# moire_v1_1.net
KiCad netlist of a schematic drawn in EAGLE
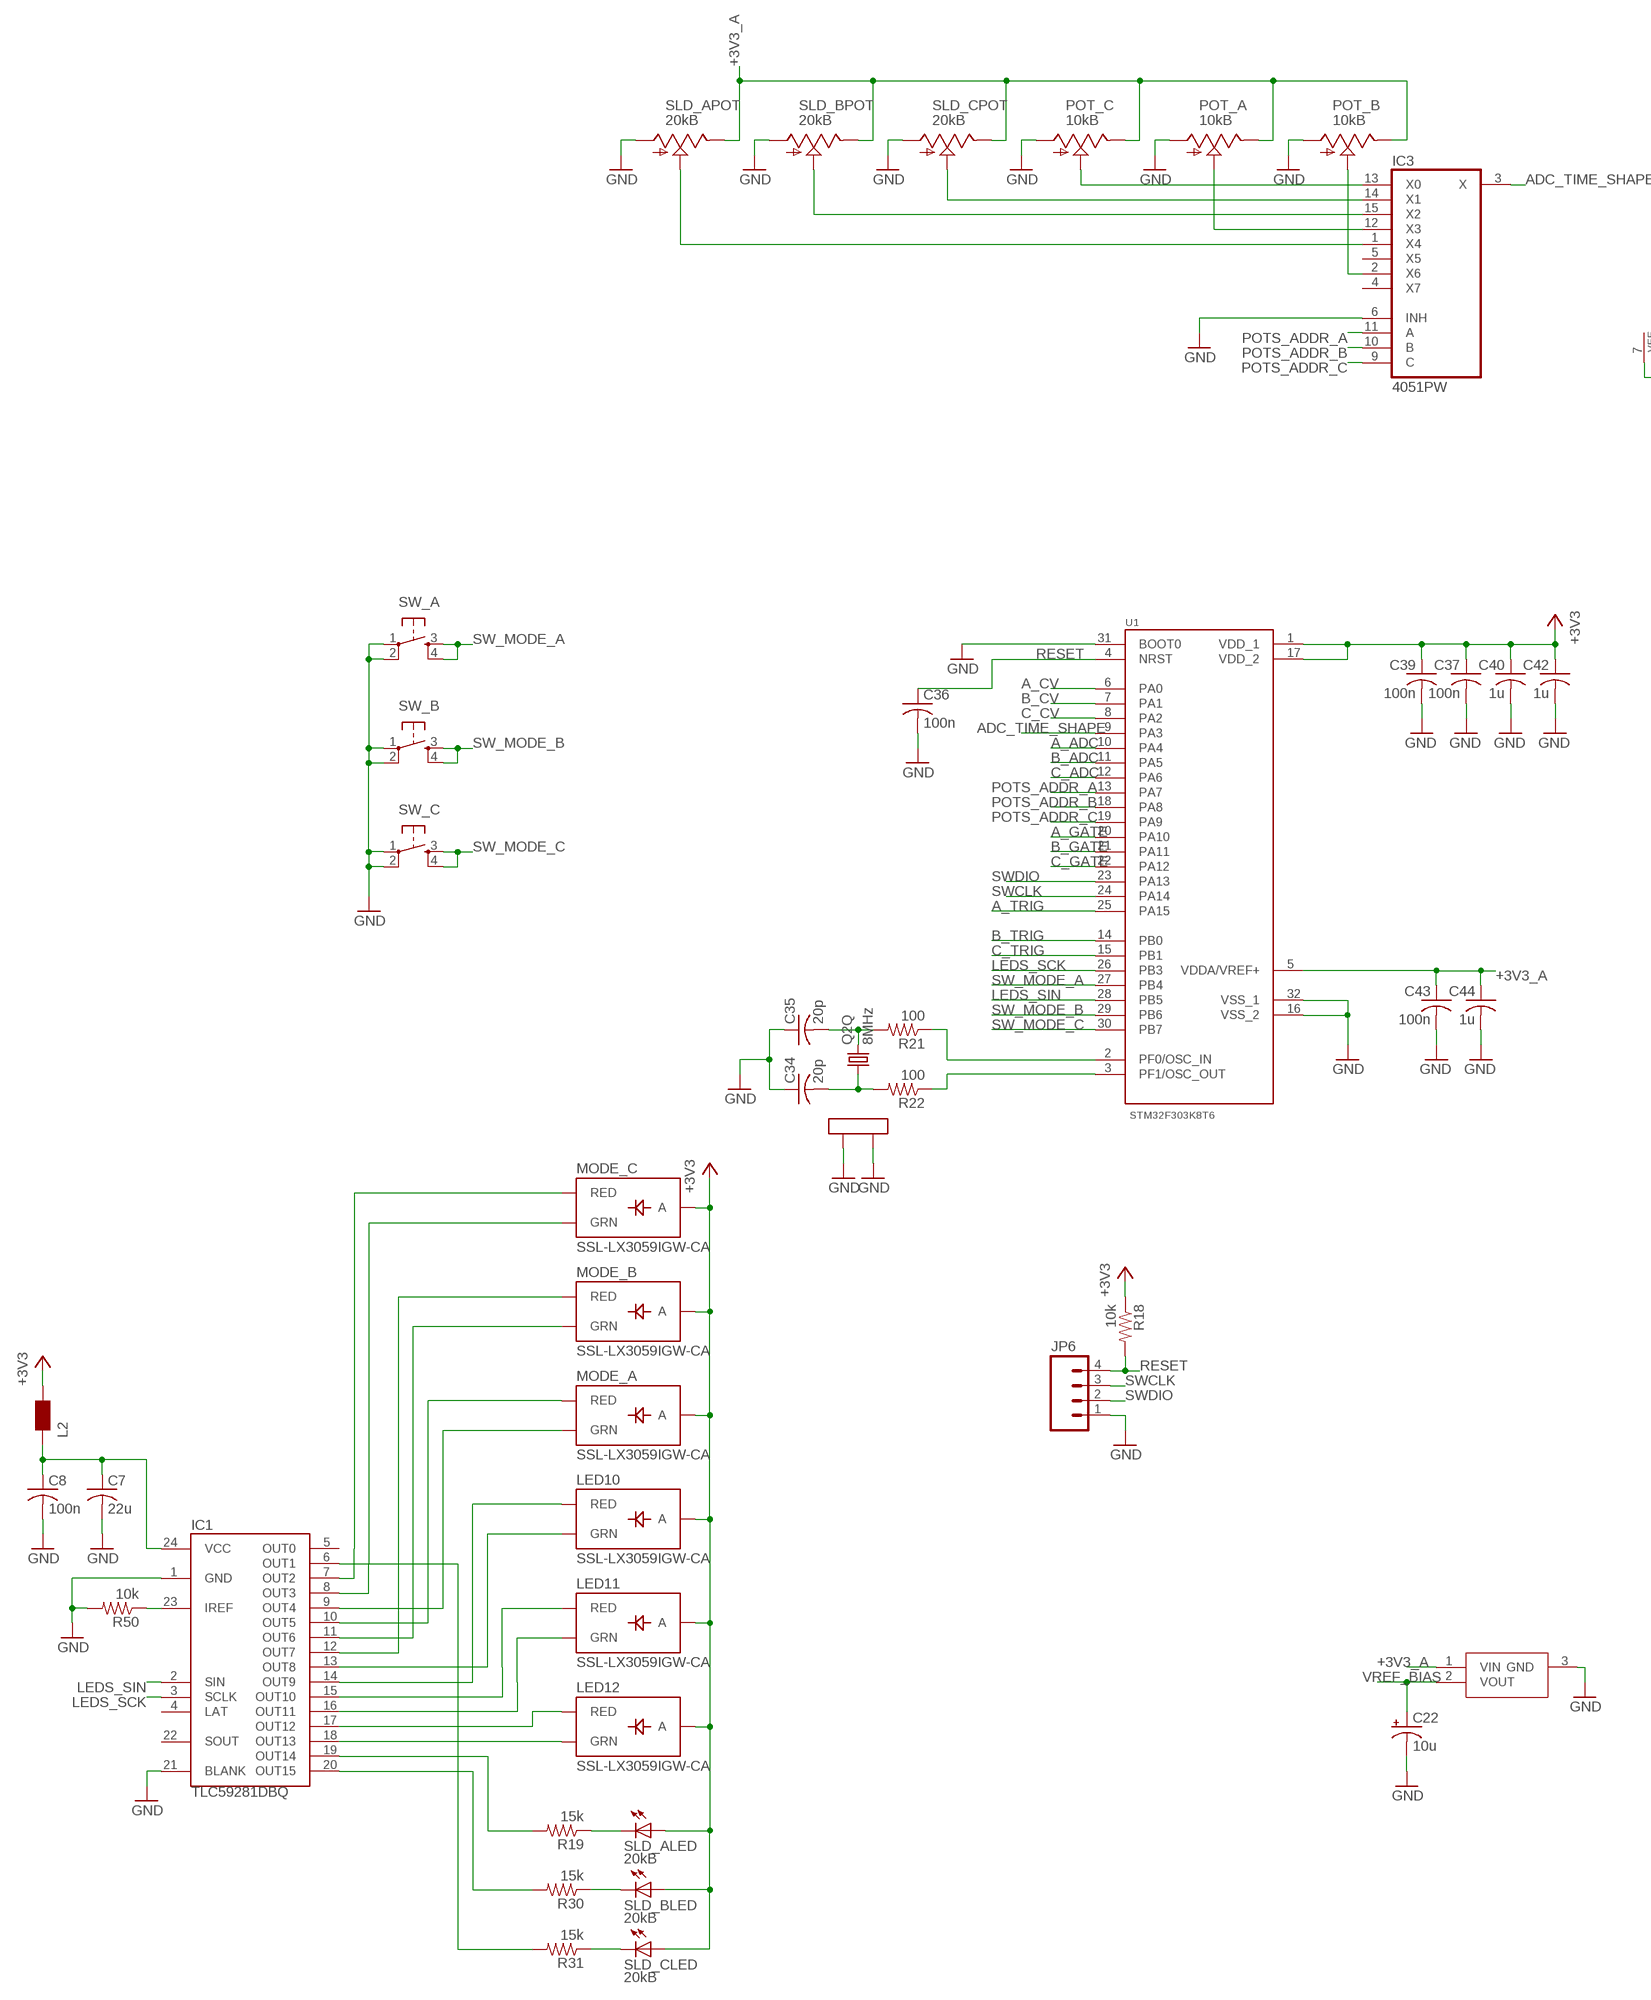
[diagram p0: schematic, sheet 1, part 1 of 2]
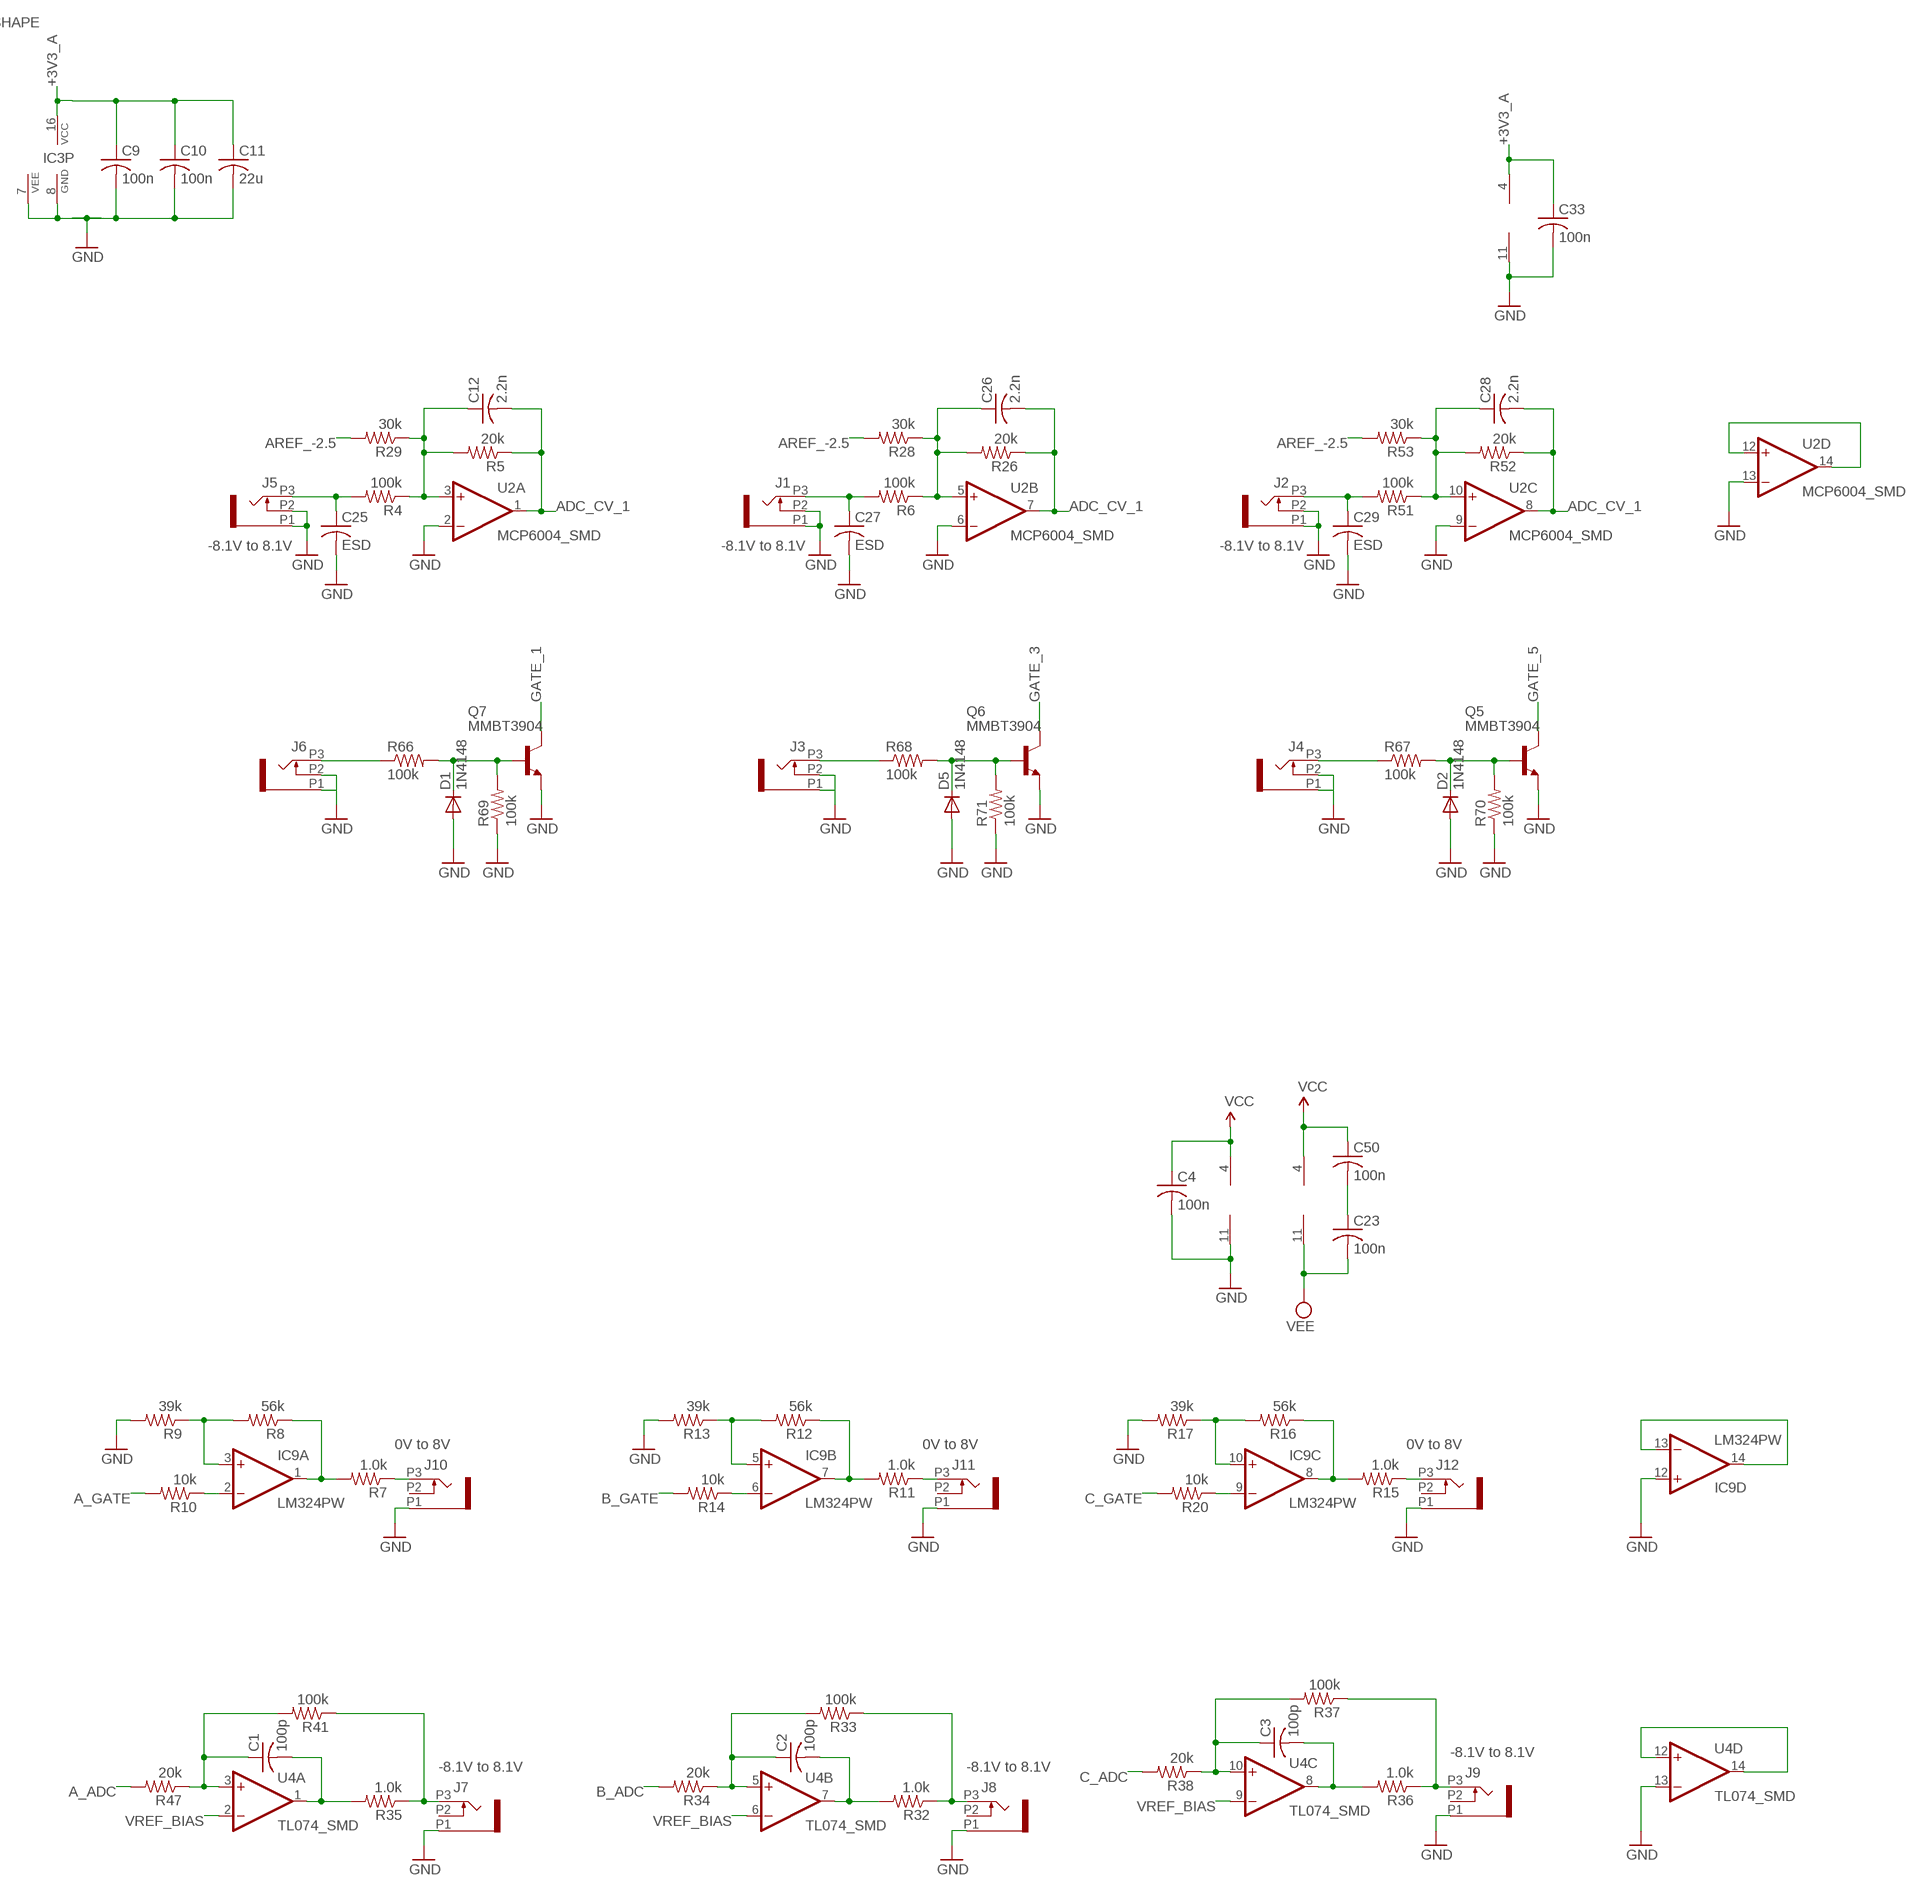
[diagram p1: schematic, sheet 1, part 2 of 2]
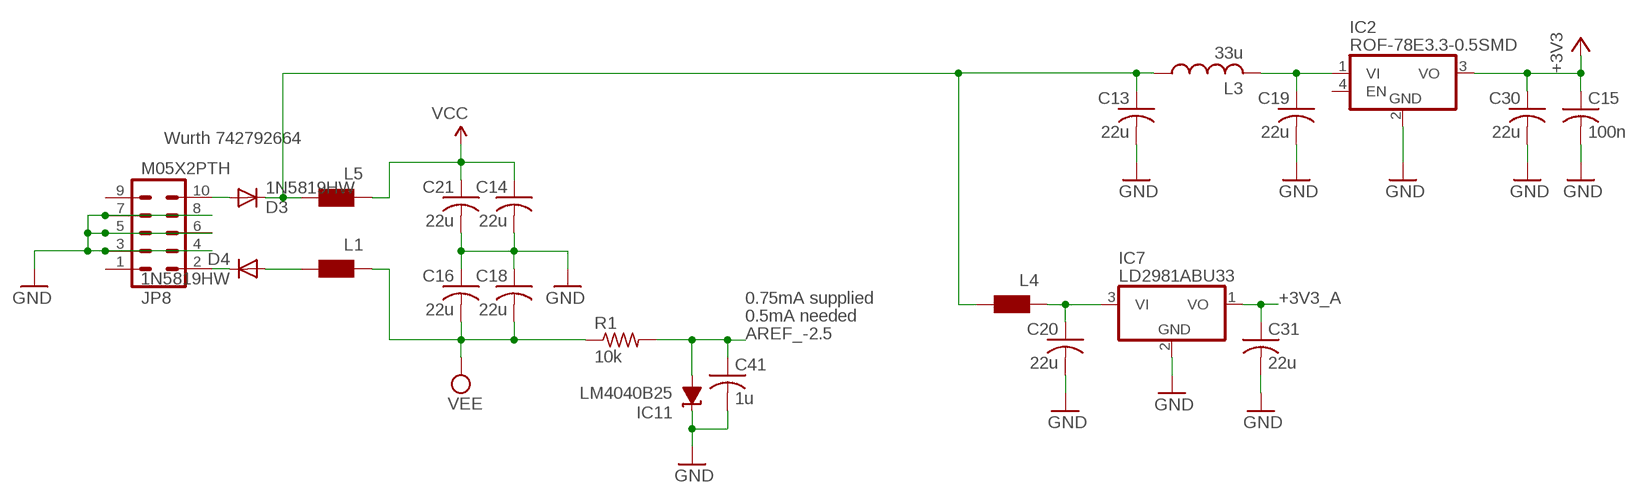
[diagram p2: schematic, sheet 2]

(export (version "E")
  (design (tool "Eeschema 10.0.6"))
  (components
    (comp (ref "C1")
      (value "100p")
      (footprint "eagle-import:C0603")
      (libsource (lib "eagle-import") (part "C-USC0603"))
    )
    (comp (ref "C2")
      (value "100p")
      (footprint "eagle-import:C0603")
      (libsource (lib "eagle-import") (part "C-USC0603"))
    )
    (comp (ref "C3")
      (value "100p")
      (footprint "eagle-import:C0603")
      (libsource (lib "eagle-import") (part "C-USC0603"))
    )
    (comp (ref "C4")
      (value "100n")
      (footprint "eagle-import:C0402")
      (libsource (lib "eagle-import") (part "C-USC0402"))
    )
    (comp (ref "C7")
      (value "22u")
      (footprint "eagle-import:C1206")
      (libsource (lib "eagle-import") (part "C-USC1206"))
    )
    (comp (ref "C8")
      (value "100n")
      (footprint "eagle-import:C0603")
      (libsource (lib "eagle-import") (part "C-USC0603"))
    )
    (comp (ref "C9")
      (value "100n")
      (footprint "eagle-import:C0603")
      (libsource (lib "eagle-import") (part "C-USC0603"))
    )
    (comp (ref "C10")
      (value "100n")
      (footprint "eagle-import:C0603")
      (libsource (lib "eagle-import") (part "C-USC0603"))
    )
    (comp (ref "C11")
      (value "22u")
      (footprint "eagle-import:C1206")
      (libsource (lib "eagle-import") (part "C-USC1206"))
    )
    (comp (ref "C12")
      (value "2.2n")
      (footprint "eagle-import:C0402")
      (libsource (lib "eagle-import") (part "C-USC0402"))
    )
    (comp (ref "C22")
      (value "10u")
      (footprint "eagle-import:PANASONIC_A")
      (libsource (lib "eagle-import") (part "CPOL-USA"))
    )
    (comp (ref "C23")
      (value "100n")
      (footprint "eagle-import:C0603")
      (libsource (lib "eagle-import") (part "C-USC0603"))
    )
    (comp (ref "C25")
      (value "ESD")
      (footprint "eagle-import:C0603")
      (libsource (lib "eagle-import") (part "C-USC0603"))
    )
    (comp (ref "C26")
      (value "2.2n")
      (footprint "eagle-import:C0402")
      (libsource (lib "eagle-import") (part "C-USC0402"))
    )
    (comp (ref "C27")
      (value "ESD")
      (footprint "eagle-import:C0603")
      (libsource (lib "eagle-import") (part "C-USC0603"))
    )
    (comp (ref "C28")
      (value "2.2n")
      (footprint "eagle-import:C0402")
      (libsource (lib "eagle-import") (part "C-USC0402"))
    )
    (comp (ref "C29")
      (value "ESD")
      (footprint "eagle-import:C0603")
      (libsource (lib "eagle-import") (part "C-USC0603"))
    )
    (comp (ref "C33")
      (value "100n")
      (footprint "eagle-import:C0603")
      (libsource (lib "eagle-import") (part "C-USC0603"))
    )
    (comp (ref "C34")
      (value "20p")
      (footprint "eagle-import:C0603")
      (libsource (lib "eagle-import") (part "C-USC0603"))
    )
    (comp (ref "C35")
      (value "20p")
      (footprint "eagle-import:C0603")
      (libsource (lib "eagle-import") (part "C-USC0603"))
    )
    (comp (ref "C36")
      (value "100n")
      (footprint "eagle-import:C0603")
      (libsource (lib "eagle-import") (part "C-USC0603"))
    )
    (comp (ref "C37")
      (value "100n")
      (footprint "eagle-import:C0603")
      (libsource (lib "eagle-import") (part "C-USC0603"))
    )
    (comp (ref "C39")
      (value "100n")
      (footprint "eagle-import:C0603")
      (libsource (lib "eagle-import") (part "C-USC0603"))
    )
    (comp (ref "C40")
      (value "1u")
      (footprint "eagle-import:C0603")
      (libsource (lib "eagle-import") (part "C-USC0603"))
    )
    (comp (ref "C42")
      (value "1u")
      (footprint "eagle-import:C0603")
      (libsource (lib "eagle-import") (part "C-USC0603"))
    )
    (comp (ref "C43")
      (value "100n")
      (footprint "eagle-import:C0603")
      (libsource (lib "eagle-import") (part "C-USC0603"))
    )
    (comp (ref "C44")
      (value "1u")
      (footprint "eagle-import:C0603")
      (libsource (lib "eagle-import") (part "C-USC0603"))
    )
    (comp (ref "C50")
      (value "100n")
      (footprint "eagle-import:C0603")
      (libsource (lib "eagle-import") (part "C-USC0603"))
    )
    (comp (ref "D1")
      (value "1N4148")
      (footprint "eagle-import:SOD523")
      (libsource (lib "eagle-import") (part "DIODE-SOD523"))
    )
    (comp (ref "D2")
      (value "1N4148")
      (footprint "eagle-import:SOD523")
      (libsource (lib "eagle-import") (part "DIODE-SOD523"))
    )
    (comp (ref "D5")
      (value "1N4148")
      (footprint "eagle-import:SOD523")
      (libsource (lib "eagle-import") (part "DIODE-SOD523"))
    )
    (comp (ref "IC1")
      (value "TLC59281DBQ")
      (footprint "eagle-import:TSSOP24_0635")
      (libsource (lib "eagle-import") (part "TLC59281DBQ"))
    )
    (comp (ref "IC3")
      (value "4051PW")
      (footprint "eagle-import:TSSOP16_065")
      (libsource (lib "eagle-import") (part "4051PW"))
    )
    (comp (ref "IC4")
      (value "LM324PW")
      (footprint "eagle-import:TSSOP14_065")
      (libsource (lib "eagle-import") (part "TL074PW"))
    )
    (comp (ref "IC9")
      (value "LM324PW")
      (footprint "eagle-import:TSSOP14_065")
      (libsource (lib "eagle-import") (part "TL074PW"))
    )
    (comp (ref "J1")
      (value "PJ301_THONKICONN6")
      (footprint "eagle-import:WQP_PJ_301M6")
      (libsource (lib "eagle-import") (part "PJ301_THONKICONN6"))
    )
    (comp (ref "J2")
      (value "PJ301_THONKICONN6")
      (footprint "eagle-import:WQP_PJ_301M6")
      (libsource (lib "eagle-import") (part "PJ301_THONKICONN6"))
    )
    (comp (ref "J3")
      (value "PJ301_THONKICONN6")
      (footprint "eagle-import:WQP_PJ_301M6")
      (libsource (lib "eagle-import") (part "PJ301_THONKICONN6"))
    )
    (comp (ref "J4")
      (value "PJ301_THONKICONN6")
      (footprint "eagle-import:WQP_PJ_301M6")
      (libsource (lib "eagle-import") (part "PJ301_THONKICONN6"))
    )
    (comp (ref "J5")
      (value "PJ301_THONKICONN6")
      (footprint "eagle-import:WQP_PJ_301M6")
      (libsource (lib "eagle-import") (part "PJ301_THONKICONN6"))
    )
    (comp (ref "J6")
      (value "PJ301_THONKICONN6")
      (footprint "eagle-import:WQP_PJ_301M6")
      (libsource (lib "eagle-import") (part "PJ301_THONKICONN6"))
    )
    (comp (ref "J7")
      (value "PJ301_THONKICONN6")
      (footprint "eagle-import:WQP_PJ_301M6")
      (libsource (lib "eagle-import") (part "PJ301_THONKICONN6"))
    )
    (comp (ref "J8")
      (value "PJ301_THONKICONN6")
      (footprint "eagle-import:WQP_PJ_301M6")
      (libsource (lib "eagle-import") (part "PJ301_THONKICONN6"))
    )
    (comp (ref "J9")
      (value "PJ301_THONKICONN6")
      (footprint "eagle-import:WQP_PJ_301M6")
      (libsource (lib "eagle-import") (part "PJ301_THONKICONN6"))
    )
    (comp (ref "J10")
      (value "PJ301_THONKICONN6")
      (footprint "eagle-import:WQP_PJ_301M6")
      (libsource (lib "eagle-import") (part "PJ301_THONKICONN6"))
    )
    (comp (ref "J11")
      (value "PJ301_THONKICONN6")
      (footprint "eagle-import:WQP_PJ_301M6")
      (libsource (lib "eagle-import") (part "PJ301_THONKICONN6"))
    )
    (comp (ref "J12")
      (value "PJ301_THONKICONN6")
      (footprint "eagle-import:WQP_PJ_301M6")
      (libsource (lib "eagle-import") (part "PJ301_THONKICONN6"))
    )
    (comp (ref "JP6")
      (value "M04PTH")
      (footprint "eagle-import:1X04")
      (libsource (lib "eagle-import") (part "M04PTH"))
    )
    (comp (ref "L2")
      (value "WE-CBF_0603")
      (footprint "eagle-import:0603")
      (libsource (lib "eagle-import") (part "WE-CBF_0603"))
    )
    (comp (ref "LED10")
      (value "SSL-LX3059IGW-CA")
      (footprint "eagle-import:LED-BICOLOR-THROUGHHOLE-LUMEX")
      (libsource (lib "eagle-import") (part "LED-BICOLOR-THROUGHHOLE-CA"))
    )
    (comp (ref "LED11")
      (value "SSL-LX3059IGW-CA")
      (footprint "eagle-import:LED-BICOLOR-THROUGHHOLE-LUMEX")
      (libsource (lib "eagle-import") (part "LED-BICOLOR-THROUGHHOLE-CA"))
    )
    (comp (ref "LED12")
      (value "SSL-LX3059IGW-CA")
      (footprint "eagle-import:LED-BICOLOR-THROUGHHOLE-LUMEX")
      (libsource (lib "eagle-import") (part "LED-BICOLOR-THROUGHHOLE-CA"))
    )
    (comp (ref "MODE_A")
      (value "SSL-LX3059IGW-CA")
      (footprint "eagle-import:LED-BICOLOR-THROUGHHOLE-LUMEX")
      (libsource (lib "eagle-import") (part "LED-BICOLOR-THROUGHHOLE-CA"))
    )
    (comp (ref "MODE_B")
      (value "SSL-LX3059IGW-CA")
      (footprint "eagle-import:LED-BICOLOR-THROUGHHOLE-LUMEX")
      (libsource (lib "eagle-import") (part "LED-BICOLOR-THROUGHHOLE-CA"))
    )
    (comp (ref "MODE_C")
      (value "SSL-LX3059IGW-CA")
      (footprint "eagle-import:LED-BICOLOR-THROUGHHOLE-LUMEX")
      (libsource (lib "eagle-import") (part "LED-BICOLOR-THROUGHHOLE-CA"))
    )
    (comp (ref "POT_A")
      (value "10kB")
      (footprint "eagle-import:ALPS_POT_VERTICAL_PS")
      (libsource (lib "eagle-import") (part "POT_USVERTICAL_PS"))
    )
    (comp (ref "POT_B")
      (value "10kB")
      (footprint "eagle-import:ALPS_POT_VERTICAL_PS")
      (libsource (lib "eagle-import") (part "POT_USVERTICAL_PS"))
    )
    (comp (ref "POT_C")
      (value "10kB")
      (footprint "eagle-import:ALPS_POT_VERTICAL_PS")
      (libsource (lib "eagle-import") (part "POT_USVERTICAL_PS"))
    )
    (comp (ref "Q2")
      (value "8MHz")
      (footprint "eagle-import:CTS406")
      (libsource (lib "eagle-import") (part "CRYSTAL"))
    )
    (comp (ref "Q5")
      (value "MMBT3904")
      (footprint "eagle-import:SOT23-BEC")
      (libsource (lib "eagle-import") (part "-NPN-SOT23-BECMMBT3904LT1"))
    )
    (comp (ref "Q6")
      (value "MMBT3904")
      (footprint "eagle-import:SOT23-BEC")
      (libsource (lib "eagle-import") (part "-NPN-SOT23-BECMMBT3904LT1"))
    )
    (comp (ref "Q7")
      (value "MMBT3904")
      (footprint "eagle-import:SOT23-BEC")
      (libsource (lib "eagle-import") (part "-NPN-SOT23-BECMMBT3904LT1"))
    )
    (comp (ref "R4")
      (value "100k")
      (footprint "eagle-import:R0402")
      (libsource (lib "eagle-import") (part "R-US_R0402"))
    )
    (comp (ref "R5")
      (value "20k")
      (footprint "eagle-import:R0402")
      (libsource (lib "eagle-import") (part "R-US_R0402"))
    )
    (comp (ref "R6")
      (value "100k")
      (footprint "eagle-import:R0402")
      (libsource (lib "eagle-import") (part "R-US_R0402"))
    )
    (comp (ref "R7")
      (value "1.0k")
      (footprint "eagle-import:R0603")
      (libsource (lib "eagle-import") (part "R-US_R0603"))
    )
    (comp (ref "R8")
      (value "56k")
      (footprint "eagle-import:R0402")
      (libsource (lib "eagle-import") (part "R-US_R0402"))
    )
    (comp (ref "R9")
      (value "39k")
      (footprint "eagle-import:R0402")
      (libsource (lib "eagle-import") (part "R-US_R0402"))
    )
    (comp (ref "R10")
      (value "10k")
      (footprint "eagle-import:R0402")
      (libsource (lib "eagle-import") (part "R-US_R0402"))
    )
    (comp (ref "R11")
      (value "1.0k")
      (footprint "eagle-import:R0603")
      (libsource (lib "eagle-import") (part "R-US_R0603"))
    )
    (comp (ref "R12")
      (value "56k")
      (footprint "eagle-import:R0402")
      (libsource (lib "eagle-import") (part "R-US_R0402"))
    )
    (comp (ref "R13")
      (value "39k")
      (footprint "eagle-import:R0402")
      (libsource (lib "eagle-import") (part "R-US_R0402"))
    )
    (comp (ref "R14")
      (value "10k")
      (footprint "eagle-import:R0402")
      (libsource (lib "eagle-import") (part "R-US_R0402"))
    )
    (comp (ref "R15")
      (value "1.0k")
      (footprint "eagle-import:R0603")
      (libsource (lib "eagle-import") (part "R-US_R0603"))
    )
    (comp (ref "R16")
      (value "56k")
      (footprint "eagle-import:R0402")
      (libsource (lib "eagle-import") (part "R-US_R0402"))
    )
    (comp (ref "R17")
      (value "39k")
      (footprint "eagle-import:R0402")
      (libsource (lib "eagle-import") (part "R-US_R0402"))
    )
    (comp (ref "R18")
      (value "10k")
      (footprint "eagle-import:R0603")
      (libsource (lib "eagle-import") (part "R-US_R0603"))
    )
    (comp (ref "R19")
      (value "15k")
      (footprint "eagle-import:R0603")
      (libsource (lib "eagle-import") (part "R-US_R0603"))
    )
    (comp (ref "R20")
      (value "10k")
      (footprint "eagle-import:R0402")
      (libsource (lib "eagle-import") (part "R-US_R0402"))
    )
    (comp (ref "R21")
      (value "100")
      (footprint "eagle-import:R0603")
      (libsource (lib "eagle-import") (part "R-US_R0603"))
    )
    (comp (ref "R22")
      (value "100")
      (footprint "eagle-import:R0603")
      (libsource (lib "eagle-import") (part "R-US_R0603"))
    )
    (comp (ref "R26")
      (value "20k")
      (footprint "eagle-import:R0402")
      (libsource (lib "eagle-import") (part "R-US_R0402"))
    )
    (comp (ref "R28")
      (value "30k")
      (footprint "eagle-import:R0402")
      (libsource (lib "eagle-import") (part "R-US_R0402"))
    )
    (comp (ref "R29")
      (value "30k")
      (footprint "eagle-import:R0402")
      (libsource (lib "eagle-import") (part "R-US_R0402"))
    )
    (comp (ref "R30")
      (value "15k")
      (footprint "eagle-import:R0603")
      (libsource (lib "eagle-import") (part "R-US_R0603"))
    )
    (comp (ref "R31")
      (value "15k")
      (footprint "eagle-import:R0603")
      (libsource (lib "eagle-import") (part "R-US_R0603"))
    )
    (comp (ref "R32")
      (value "1.0k")
      (footprint "eagle-import:R0603")
      (libsource (lib "eagle-import") (part "R-US_R0603"))
    )
    (comp (ref "R33")
      (value "100k")
      (footprint "eagle-import:R0603")
      (libsource (lib "eagle-import") (part "R-US_R0603"))
    )
    (comp (ref "R34")
      (value "20k")
      (footprint "eagle-import:R0603")
      (libsource (lib "eagle-import") (part "R-US_R0603"))
    )
    (comp (ref "R35")
      (value "1.0k")
      (footprint "eagle-import:R0603")
      (libsource (lib "eagle-import") (part "R-US_R0603"))
    )
    (comp (ref "R36")
      (value "1.0k")
      (footprint "eagle-import:R0603")
      (libsource (lib "eagle-import") (part "R-US_R0603"))
    )
    (comp (ref "R37")
      (value "100k")
      (footprint "eagle-import:R0603")
      (libsource (lib "eagle-import") (part "R-US_R0603"))
    )
    (comp (ref "R38")
      (value "20k")
      (footprint "eagle-import:R0603")
      (libsource (lib "eagle-import") (part "R-US_R0603"))
    )
    (comp (ref "R41")
      (value "100k")
      (footprint "eagle-import:R0603")
      (libsource (lib "eagle-import") (part "R-US_R0603"))
    )
    (comp (ref "R47")
      (value "20k")
      (footprint "eagle-import:R0603")
      (libsource (lib "eagle-import") (part "R-US_R0603"))
    )
    (comp (ref "R50")
      (value "10k")
      (footprint "eagle-import:R0603")
      (libsource (lib "eagle-import") (part "R-US_R0603"))
    )
    (comp (ref "R51")
      (value "100k")
      (footprint "eagle-import:R0402")
      (libsource (lib "eagle-import") (part "R-US_R0402"))
    )
    (comp (ref "R52")
      (value "20k")
      (footprint "eagle-import:R0402")
      (libsource (lib "eagle-import") (part "R-US_R0402"))
    )
    (comp (ref "R53")
      (value "30k")
      (footprint "eagle-import:R0402")
      (libsource (lib "eagle-import") (part "R-US_R0402"))
    )
    (comp (ref "R66")
      (value "100k")
      (footprint "eagle-import:R0402")
      (libsource (lib "eagle-import") (part "R-US_R0402"))
    )
    (comp (ref "R67")
      (value "100k")
      (footprint "eagle-import:R0402")
      (libsource (lib "eagle-import") (part "R-US_R0402"))
    )
    (comp (ref "R68")
      (value "100k")
      (footprint "eagle-import:R0402")
      (libsource (lib "eagle-import") (part "R-US_R0402"))
    )
    (comp (ref "R69")
      (value "100k")
      (footprint "eagle-import:R0402")
      (libsource (lib "eagle-import") (part "R-US_R0402"))
    )
    (comp (ref "R70")
      (value "100k")
      (footprint "eagle-import:R0402")
      (libsource (lib "eagle-import") (part "R-US_R0402"))
    )
    (comp (ref "R71")
      (value "100k")
      (footprint "eagle-import:R0402")
      (libsource (lib "eagle-import") (part "R-US_R0402"))
    )
    (comp (ref "SLD_A")
      (value "20kB")
      (footprint "eagle-import:BOURNS_SLIDER")
      (libsource (lib "eagle-import") (part "BOURNS_SLIDER"))
    )
    (comp (ref "SLD_B")
      (value "20kB")
      (footprint "eagle-import:BOURNS_SLIDER")
      (libsource (lib "eagle-import") (part "BOURNS_SLIDER"))
    )
    (comp (ref "SLD_C")
      (value "20kB")
      (footprint "eagle-import:BOURNS_SLIDER")
      (libsource (lib "eagle-import") (part "BOURNS_SLIDER"))
    )
    (comp (ref "SW_A")
      (value "TAC_SWITCHPTH")
      (footprint "eagle-import:TACTILE-PTH")
      (libsource (lib "eagle-import") (part "TAC_SWITCHPTH"))
    )
    (comp (ref "SW_B")
      (value "TAC_SWITCHPTH")
      (footprint "eagle-import:TACTILE-PTH")
      (libsource (lib "eagle-import") (part "TAC_SWITCHPTH"))
    )
    (comp (ref "SW_C")
      (value "TAC_SWITCHPTH")
      (footprint "eagle-import:TACTILE-PTH")
      (libsource (lib "eagle-import") (part "TAC_SWITCHPTH"))
    )
    (comp (ref "U$1")
      (value "ISL21010")
      (footprint "eagle-import:SOT-23-3")
      (libsource (lib "eagle-import") (part "ISL21010"))
    )
    (comp (ref "U1")
      (value "STM32F303K8T6")
      (footprint "eagle-import:QFP80P900X900X160-32N")
      (fields (field (name "MF") "STMicroelectronics"))
      (libsource (lib "eagle-import") (part "STM32F303K8T6"))
    )
    (comp (ref "U2")
      (value "MCP6004_SMD")
      (footprint "eagle-import:SO14")
      (libsource (lib "eagle-import") (part "MCP6004_SMD"))
    )
    (comp (ref "U4")
      (value "TL074_SMD")
      (footprint "eagle-import:SO14")
      (libsource (lib "eagle-import") (part "TL074_SMD"))
    )
    (comp (ref "C13")
      (value "22u")
      (footprint "eagle-import:C1206")
      (libsource (lib "eagle-import") (part "C-USC1206"))
    )
    (comp (ref "C14")
      (value "22u")
      (footprint "eagle-import:C1206")
      (libsource (lib "eagle-import") (part "C-USC1206"))
    )
    (comp (ref "C15")
      (value "100n")
      (footprint "eagle-import:C0402")
      (libsource (lib "eagle-import") (part "C-USC0402"))
    )
    (comp (ref "C16")
      (value "22u")
      (footprint "eagle-import:C1206")
      (libsource (lib "eagle-import") (part "C-USC1206"))
    )
    (comp (ref "C18")
      (value "22u")
      (footprint "eagle-import:C1206")
      (libsource (lib "eagle-import") (part "C-USC1206"))
    )
    (comp (ref "C19")
      (value "22u")
      (footprint "eagle-import:C1206")
      (libsource (lib "eagle-import") (part "C-USC1206"))
    )
    (comp (ref "C20")
      (value "22u")
      (footprint "eagle-import:C1206")
      (libsource (lib "eagle-import") (part "C-USC1206"))
    )
    (comp (ref "C21")
      (value "22u")
      (footprint "eagle-import:C1206")
      (libsource (lib "eagle-import") (part "C-USC1206"))
    )
    (comp (ref "C30")
      (value "22u")
      (footprint "eagle-import:C1206")
      (libsource (lib "eagle-import") (part "C-USC1206"))
    )
    (comp (ref "C31")
      (value "22u")
      (footprint "eagle-import:C1206")
      (libsource (lib "eagle-import") (part "C-USC1206"))
    )
    (comp (ref "C41")
      (value "1u")
      (footprint "eagle-import:C0402")
      (libsource (lib "eagle-import") (part "C-USC0402"))
    )
    (comp (ref "D3")
      (value "1N5819HW")
      (footprint "eagle-import:SOD123")
      (libsource (lib "eagle-import") (part "DIODE-SOD123"))
    )
    (comp (ref "D4")
      (value "1N5819HW")
      (footprint "eagle-import:SOD123")
      (libsource (lib "eagle-import") (part "DIODE-SOD123"))
    )
    (comp (ref "IC2")
      (value "ROF-78E3.3-0.5SMD")
      (footprint "eagle-import:ROF78EXX-0.5SMD")
      (libsource (lib "eagle-import") (part "ROF-78EXX-0.55SMD"))
    )
    (comp (ref "IC7")
      (value "LD2981ABU33")
      (footprint "eagle-import:SOT89")
      (libsource (lib "eagle-import") (part "LD2981ABU"))
    )
    (comp (ref "IC11")
      (value "LM4040B25")
      (footprint "eagle-import:DBZ_R-PDSO-G3")
      (libsource (lib "eagle-import") (part "LM4041DBZB12"))
    )
    (comp (ref "JP8")
      (value "M05X2PTH")
      (footprint "eagle-import:2X5-PTH")
      (libsource (lib "eagle-import") (part "M05X2PTH"))
    )
    (comp (ref "L1")
      (value "WE-CBF_0603")
      (footprint "eagle-import:0603")
      (libsource (lib "eagle-import") (part "WE-CBF_0603"))
    )
    (comp (ref "L3")
      (value "33u")
      (footprint "eagle-import:L2012C")
      (libsource (lib "eagle-import") (part "L-USL2012C"))
    )
    (comp (ref "L4")
      (value "WE-CBF_0603")
      (footprint "eagle-import:0603")
      (libsource (lib "eagle-import") (part "WE-CBF_0603"))
    )
    (comp (ref "L5")
      (value "WE-CBF_0603")
      (footprint "eagle-import:0603")
      (libsource (lib "eagle-import") (part "WE-CBF_0603"))
    )
    (comp (ref "R1")
      (value "10k")
      (footprint "eagle-import:R0402")
      (libsource (lib "eagle-import") (part "R-US_R0402"))
    )
  )
  (nets
    (net (code "1") (name "+3V3") (class "Default")
      (node (ref "C15") (pin "1") (pinfunction "1_1") (pintype "passive"))
      (node (ref "C30") (pin "1") (pinfunction "1_1") (pintype "passive"))
      (node (ref "C37") (pin "1") (pinfunction "1_1") (pintype "passive"))
      (node (ref "C39") (pin "1") (pinfunction "1_1") (pintype "passive"))
      (node (ref "C40") (pin "1") (pinfunction "1_1") (pintype "passive"))
      (node (ref "C42") (pin "1") (pinfunction "1_1") (pintype "passive"))
      (node (ref "IC2") (pin "3") (pinfunction "VO_3") (pintype "passive"))
      (node (ref "L2") (pin "2") (pinfunction "2_2") (pintype "passive"))
      (node (ref "LED10") (pin "A") (pinfunction "A_A") (pintype "bidirectional"))
      (node (ref "LED11") (pin "A") (pinfunction "A_A") (pintype "bidirectional"))
      (node (ref "LED12") (pin "A") (pinfunction "A_A") (pintype "bidirectional"))
      (node (ref "MODE_A") (pin "A") (pinfunction "A_A") (pintype "bidirectional"))
      (node (ref "MODE_B") (pin "A") (pinfunction "A_A") (pintype "bidirectional"))
      (node (ref "MODE_C") (pin "A") (pinfunction "A_A") (pintype "bidirectional"))
      (node (ref "R18") (pin "1") (pinfunction "1_1") (pintype "passive"))
      (node (ref "SLD_A") (pin "B") (pinfunction "A_B") (pintype "passive"))
      (node (ref "SLD_B") (pin "B") (pinfunction "A_B") (pintype "passive"))
      (node (ref "SLD_C") (pin "B") (pinfunction "A_B") (pintype "passive"))
      (node (ref "U1") (pin "1") (pinfunction "VDD_1_1") (pintype "power_in"))
      (node (ref "U1") (pin "17") (pinfunction "VDD_2_17") (pintype "power_in"))
    )
    (net (code "2") (name "+3V3_A") (class "Default")
      (node (ref "C10") (pin "1") (pinfunction "1_1") (pintype "passive"))
      (node (ref "C11") (pin "1") (pinfunction "1_1") (pintype "passive"))
      (node (ref "C31") (pin "1") (pinfunction "1_1") (pintype "passive"))
      (node (ref "C33") (pin "1") (pinfunction "1_1") (pintype "passive"))
      (node (ref "C43") (pin "1") (pinfunction "1_1") (pintype "passive"))
      (node (ref "C44") (pin "1") (pinfunction "1_1") (pintype "passive"))
      (node (ref "C9") (pin "1") (pinfunction "1_1") (pintype "passive"))
      (node (ref "IC3") (pin "16") (pinfunction "VCC_16") (pintype "power_in"))
      (node (ref "IC7") (pin "1") (pinfunction "VO_1") (pintype "passive"))
      (node (ref "POT_A") (pin "P$1") (pinfunction "E_P$1") (pintype "passive"))
      (node (ref "POT_B") (pin "P$1") (pinfunction "E_P$1") (pintype "passive"))
      (node (ref "POT_C") (pin "P$1") (pinfunction "E_P$1") (pintype "passive"))
      (node (ref "SLD_A") (pin "3") (pinfunction "E_3") (pintype "passive"))
      (node (ref "SLD_B") (pin "3") (pinfunction "E_3") (pintype "passive"))
      (node (ref "SLD_C") (pin "3") (pinfunction "E_3") (pintype "passive"))
      (node (ref "U$1") (pin "1") (pinfunction "VIN_1") (pintype "input"))
      (node (ref "U1") (pin "5") (pinfunction "VDDA/VREF+_5") (pintype "power_in"))
      (node (ref "U2") (pin "4") (pinfunction "V+_4") (pintype "power_in"))
    )
    (net (code "3") (name "ADC_CV_1") (class "Default")
      (node (ref "C12") (pin "2") (pinfunction "2_2") (pintype "passive"))
      (node (ref "C26") (pin "2") (pinfunction "2_2") (pintype "passive"))
      (node (ref "C28") (pin "2") (pinfunction "2_2") (pintype "passive"))
      (node (ref "R26") (pin "1") (pinfunction "1_1") (pintype "passive"))
      (node (ref "R5") (pin "1") (pinfunction "1_1") (pintype "passive"))
      (node (ref "R52") (pin "1") (pinfunction "1_1") (pintype "passive"))
      (node (ref "U2") (pin "1") (pinfunction "OUT_1") (pintype "output"))
      (node (ref "U2") (pin "7") (pinfunction "OUT_7") (pintype "output"))
      (node (ref "U2") (pin "8") (pinfunction "OUT_8") (pintype "output"))
    )
    (net (code "4") (name "ADC_TIME_SHAPE") (class "Default")
      (node (ref "IC3") (pin "3") (pinfunction "X_3") (pintype "bidirectional"))
      (node (ref "U1") (pin "9") (pinfunction "PA3_9") (pintype "bidirectional"))
    )
    (net (code "5") (name "AREF_-2.5") (class "Default")
      (node (ref "C41") (pin "1") (pinfunction "1_1") (pintype "passive"))
      (node (ref "IC11") (pin "2") (pinfunction "A_2") (pintype "passive"))
      (node (ref "R1") (pin "2") (pinfunction "2_2") (pintype "passive"))
      (node (ref "R28") (pin "2") (pinfunction "2_2") (pintype "passive"))
      (node (ref "R29") (pin "2") (pinfunction "2_2") (pintype "passive"))
      (node (ref "R53") (pin "2") (pinfunction "2_2") (pintype "passive"))
    )
    (net (code "6") (name "A_ADC") (class "Default")
      (node (ref "R47") (pin "2") (pinfunction "2_2") (pintype "passive"))
      (node (ref "U1") (pin "10") (pinfunction "PA4_10") (pintype "bidirectional"))
    )
    (net (code "7") (name "A_CV") (class "Default")
      (node (ref "U1") (pin "6") (pinfunction "PA0_6") (pintype "bidirectional"))
    )
    (net (code "8") (name "A_GATE") (class "Default")
      (node (ref "R10") (pin "2") (pinfunction "2_2") (pintype "passive"))
      (node (ref "U1") (pin "20") (pinfunction "PA10_20") (pintype "bidirectional"))
    )
    (net (code "9") (name "A_TRIG") (class "Default")
      (node (ref "U1") (pin "25") (pinfunction "PA15_25") (pintype "bidirectional"))
    )
    (net (code "10") (name "B_ADC") (class "Default")
      (node (ref "R34") (pin "2") (pinfunction "2_2") (pintype "passive"))
      (node (ref "U1") (pin "11") (pinfunction "PA5_11") (pintype "bidirectional"))
    )
    (net (code "11") (name "B_CV") (class "Default")
      (node (ref "U1") (pin "7") (pinfunction "PA1_7") (pintype "bidirectional"))
    )
    (net (code "12") (name "B_GATE") (class "Default")
      (node (ref "R14") (pin "2") (pinfunction "2_2") (pintype "passive"))
      (node (ref "U1") (pin "21") (pinfunction "PA11_21") (pintype "bidirectional"))
    )
    (net (code "13") (name "B_TRIG") (class "Default")
      (node (ref "U1") (pin "14") (pinfunction "PB0_14") (pintype "bidirectional"))
    )
    (net (code "14") (name "C_ADC") (class "Default")
      (node (ref "R38") (pin "2") (pinfunction "2_2") (pintype "passive"))
      (node (ref "U1") (pin "12") (pinfunction "PA6_12") (pintype "bidirectional"))
    )
    (net (code "15") (name "C_CV") (class "Default")
      (node (ref "U1") (pin "8") (pinfunction "PA2_8") (pintype "bidirectional"))
    )
    (net (code "16") (name "C_GATE") (class "Default")
      (node (ref "R20") (pin "2") (pinfunction "2_2") (pintype "passive"))
      (node (ref "U1") (pin "22") (pinfunction "PA12_22") (pintype "bidirectional"))
    )
    (net (code "17") (name "C_TRIG") (class "Default")
      (node (ref "U1") (pin "15") (pinfunction "PB1_15") (pintype "bidirectional"))
    )
    (net (code "18") (name "GATE_1") (class "Default")
      (node (ref "Q7") (pin "C") (pinfunction "C_C") (pintype "passive"))
    )
    (net (code "19") (name "GATE_3") (class "Default")
      (node (ref "Q6") (pin "C") (pinfunction "C_C") (pintype "passive"))
    )
    (net (code "20") (name "GATE_5") (class "Default")
      (node (ref "Q5") (pin "C") (pinfunction "C_C") (pintype "passive"))
    )
    (net (code "21") (name "GND") (class "Default")
      (node (ref "C10") (pin "2") (pinfunction "2_2") (pintype "passive"))
      (node (ref "C11") (pin "2") (pinfunction "2_2") (pintype "passive"))
      (node (ref "C13") (pin "2") (pinfunction "2_2") (pintype "passive"))
      (node (ref "C14") (pin "2") (pinfunction "2_2") (pintype "passive"))
      (node (ref "C15") (pin "2") (pinfunction "2_2") (pintype "passive"))
      (node (ref "C16") (pin "1") (pinfunction "1_1") (pintype "passive"))
      (node (ref "C18") (pin "1") (pinfunction "1_1") (pintype "passive"))
      (node (ref "C19") (pin "2") (pinfunction "2_2") (pintype "passive"))
      (node (ref "C20") (pin "2") (pinfunction "2_2") (pintype "passive"))
      (node (ref "C21") (pin "2") (pinfunction "2_2") (pintype "passive"))
      (node (ref "C22") (pin "-") (pinfunction "-_-") (pintype "passive"))
      (node (ref "C25") (pin "2") (pinfunction "2_2") (pintype "passive"))
      (node (ref "C27") (pin "2") (pinfunction "2_2") (pintype "passive"))
      (node (ref "C29") (pin "2") (pinfunction "2_2") (pintype "passive"))
      (node (ref "C30") (pin "2") (pinfunction "2_2") (pintype "passive"))
      (node (ref "C31") (pin "2") (pinfunction "2_2") (pintype "passive"))
      (node (ref "C33") (pin "2") (pinfunction "2_2") (pintype "passive"))
      (node (ref "C34") (pin "1") (pinfunction "1_1") (pintype "passive"))
      (node (ref "C35") (pin "1") (pinfunction "1_1") (pintype "passive"))
      (node (ref "C36") (pin "2") (pinfunction "2_2") (pintype "passive"))
      (node (ref "C37") (pin "2") (pinfunction "2_2") (pintype "passive"))
      (node (ref "C39") (pin "2") (pinfunction "2_2") (pintype "passive"))
      (node (ref "C4") (pin "2") (pinfunction "2_2") (pintype "passive"))
      (node (ref "C40") (pin "2") (pinfunction "2_2") (pintype "passive"))
      (node (ref "C41") (pin "2") (pinfunction "2_2") (pintype "passive"))
      (node (ref "C42") (pin "2") (pinfunction "2_2") (pintype "passive"))
      (node (ref "C43") (pin "2") (pinfunction "2_2") (pintype "passive"))
      (node (ref "C44") (pin "2") (pinfunction "2_2") (pintype "passive"))
      (node (ref "C7") (pin "2") (pinfunction "2_2") (pintype "passive"))
      (node (ref "C8") (pin "2") (pinfunction "2_2") (pintype "passive"))
      (node (ref "C9") (pin "2") (pinfunction "2_2") (pintype "passive"))
      (node (ref "D1") (pin "A") (pinfunction "A_A") (pintype "passive"))
      (node (ref "D2") (pin "A") (pinfunction "A_A") (pintype "passive"))
      (node (ref "D5") (pin "A") (pinfunction "A_A") (pintype "passive"))
      (node (ref "IC1") (pin "1") (pinfunction "GND_1") (pintype "bidirectional"))
      (node (ref "IC1") (pin "21") (pinfunction "BLANK_21") (pintype "bidirectional"))
      (node (ref "IC11") (pin "1") (pinfunction "C_1") (pintype "passive"))
      (node (ref "IC2") (pin "2") (pinfunction "GND_2") (pintype "passive"))
      (node (ref "IC3") (pin "6") (pinfunction "INH_6") (pintype "input"))
      (node (ref "IC3") (pin "7") (pinfunction "VEE_7") (pintype "power_in"))
      (node (ref "IC3") (pin "8") (pinfunction "GND_8") (pintype "power_in"))
      (node (ref "IC4") (pin "11") (pinfunction "V-_11") (pintype "power_in"))
      (node (ref "IC7") (pin "2") (pinfunction "GND_2") (pintype "passive"))
      (node (ref "IC9") (pin "12") (pinfunction "+IN_12") (pintype "input"))
      (node (ref "J1") (pin "P1") (pinfunction "1_P1") (pintype "passive"))
      (node (ref "J1") (pin "P2") (pinfunction "2_P2") (pintype "passive"))
      (node (ref "J10") (pin "P1") (pinfunction "1_P1") (pintype "passive"))
      (node (ref "J11") (pin "P1") (pinfunction "1_P1") (pintype "passive"))
      (node (ref "J12") (pin "P1") (pinfunction "1_P1") (pintype "passive"))
      (node (ref "J2") (pin "P1") (pinfunction "1_P1") (pintype "passive"))
      (node (ref "J2") (pin "P2") (pinfunction "2_P2") (pintype "passive"))
      (node (ref "J3") (pin "P1") (pinfunction "1_P1") (pintype "passive"))
      (node (ref "J3") (pin "P2") (pinfunction "2_P2") (pintype "passive"))
      (node (ref "J4") (pin "P1") (pinfunction "1_P1") (pintype "passive"))
      (node (ref "J4") (pin "P2") (pinfunction "2_P2") (pintype "passive"))
      (node (ref "J5") (pin "P1") (pinfunction "1_P1") (pintype "passive"))
      (node (ref "J5") (pin "P2") (pinfunction "2_P2") (pintype "passive"))
      (node (ref "J6") (pin "P1") (pinfunction "1_P1") (pintype "passive"))
      (node (ref "J6") (pin "P2") (pinfunction "2_P2") (pintype "passive"))
      (node (ref "J7") (pin "P1") (pinfunction "1_P1") (pintype "passive"))
      (node (ref "J8") (pin "P1") (pinfunction "1_P1") (pintype "passive"))
      (node (ref "J9") (pin "P1") (pinfunction "1_P1") (pintype "passive"))
      (node (ref "JP6") (pin "1") (pinfunction "1_1") (pintype "passive"))
      (node (ref "JP8") (pin "3") (pinfunction "3_3") (pintype "passive"))
      (node (ref "JP8") (pin "4") (pinfunction "4_4") (pintype "passive"))
      (node (ref "JP8") (pin "5") (pinfunction "5_5") (pintype "passive"))
      (node (ref "JP8") (pin "6") (pinfunction "6_6") (pintype "passive"))
      (node (ref "JP8") (pin "7") (pinfunction "7_7") (pintype "passive"))
      (node (ref "JP8") (pin "8") (pinfunction "8_8") (pintype "passive"))
      (node (ref "POT_A") (pin "P$3") (pinfunction "A_P$3") (pintype "passive"))
      (node (ref "POT_B") (pin "P$3") (pinfunction "A_P$3") (pintype "passive"))
      (node (ref "POT_C") (pin "P$3") (pinfunction "A_P$3") (pintype "passive"))
      (node (ref "Q2") (pin "2") (pinfunction "LID1_2") (pintype "power_in"))
      (node (ref "Q2") (pin "4") (pinfunction "LID2_4") (pintype "power_in"))
      (node (ref "Q5") (pin "E") (pinfunction "E_E") (pintype "passive"))
      (node (ref "Q6") (pin "E") (pinfunction "E_E") (pintype "passive"))
      (node (ref "Q7") (pin "E") (pinfunction "E_E") (pintype "passive"))
      (node (ref "R13") (pin "2") (pinfunction "2_2") (pintype "passive"))
      (node (ref "R17") (pin "2") (pinfunction "2_2") (pintype "passive"))
      (node (ref "R50") (pin "2") (pinfunction "2_2") (pintype "passive"))
      (node (ref "R69") (pin "1") (pinfunction "1_1") (pintype "passive"))
      (node (ref "R70") (pin "1") (pinfunction "1_1") (pintype "passive"))
      (node (ref "R71") (pin "1") (pinfunction "1_1") (pintype "passive"))
      (node (ref "R9") (pin "2") (pinfunction "2_2") (pintype "passive"))
      (node (ref "SLD_A") (pin "1") (pinfunction "A_1") (pintype "passive"))
      (node (ref "SLD_B") (pin "1") (pinfunction "A_1") (pintype "passive"))
      (node (ref "SLD_C") (pin "1") (pinfunction "A_1") (pintype "passive"))
      (node (ref "SW_A") (pin "1") (pinfunction "1_1") (pintype "passive"))
      (node (ref "SW_A") (pin "2") (pinfunction "2_2") (pintype "passive"))
      (node (ref "SW_B") (pin "1") (pinfunction "1_1") (pintype "passive"))
      (node (ref "SW_B") (pin "2") (pinfunction "2_2") (pintype "passive"))
      (node (ref "SW_C") (pin "1") (pinfunction "1_1") (pintype "passive"))
      (node (ref "SW_C") (pin "2") (pinfunction "2_2") (pintype "passive"))
      (node (ref "U$1") (pin "3") (pinfunction "GND_3") (pintype "power_in"))
      (node (ref "U1") (pin "16") (pinfunction "VSS_2_16") (pintype "power_in"))
      (node (ref "U1") (pin "31") (pinfunction "BOOT0_31") (pintype "input"))
      (node (ref "U1") (pin "32") (pinfunction "VSS_1_32") (pintype "power_in"))
      (node (ref "U2") (pin "11") (pinfunction "V-_11") (pintype "power_in"))
      (node (ref "U2") (pin "13") (pinfunction "-IN_13") (pintype "input"))
      (node (ref "U2") (pin "2") (pinfunction "-IN_2") (pintype "input"))
      (node (ref "U2") (pin "6") (pinfunction "-IN_6") (pintype "input"))
      (node (ref "U2") (pin "9") (pinfunction "-IN_9") (pintype "input"))
      (node (ref "U4") (pin "13") (pinfunction "-IN_13") (pintype "input"))
    )
    (net (code "22") (name "LEDS_SCK") (class "Default")
      (node (ref "IC1") (pin "3") (pinfunction "SCLK_3") (pintype "bidirectional"))
      (node (ref "U1") (pin "26") (pinfunction "PB3_26") (pintype "bidirectional"))
    )
    (net (code "23") (name "LEDS_SIN") (class "Default")
      (node (ref "IC1") (pin "2") (pinfunction "SIN_2") (pintype "bidirectional"))
      (node (ref "U1") (pin "28") (pinfunction "PB5_28") (pintype "bidirectional"))
    )
    (net (code "24") (name "Net-(C13-Pad1)") (class "Default")
      (node (ref "C13") (pin "1") (pinfunction "1_1") (pintype "passive"))
      (node (ref "D3") (pin "C") (pinfunction "C_C") (pintype "passive"))
      (node (ref "L3") (pin "1") (pinfunction "1_1") (pintype "passive"))
      (node (ref "L4") (pin "2") (pinfunction "2_2") (pintype "passive"))
      (node (ref "L5") (pin "2") (pinfunction "2_2") (pintype "passive"))
    )
    (net (code "25") (name "Net-(C23-Pad1)") (class "Default")
      (node (ref "C23") (pin "1") (pinfunction "1_1") (pintype "passive"))
      (node (ref "C50") (pin "2") (pinfunction "2_2") (pintype "passive"))
    )
    (net (code "26") (name "Net-(C34-Pad2)") (class "Default")
      (node (ref "C34") (pin "2") (pinfunction "2_2") (pintype "passive"))
      (node (ref "Q2") (pin "1") (pinfunction "1_1") (pintype "passive"))
      (node (ref "R22") (pin "2") (pinfunction "2_2") (pintype "passive"))
    )
    (net (code "27") (name "Net-(D1-PadC)") (class "Default")
      (node (ref "D1") (pin "C") (pinfunction "C_C") (pintype "passive"))
      (node (ref "Q7") (pin "B") (pinfunction "B_B") (pintype "passive"))
      (node (ref "R66") (pin "2") (pinfunction "2_2") (pintype "passive"))
      (node (ref "R69") (pin "2") (pinfunction "2_2") (pintype "passive"))
    )
    (net (code "28") (name "Net-(D2-PadC)") (class "Default")
      (node (ref "D2") (pin "C") (pinfunction "C_C") (pintype "passive"))
      (node (ref "Q5") (pin "B") (pinfunction "B_B") (pintype "passive"))
      (node (ref "R67") (pin "2") (pinfunction "2_2") (pintype "passive"))
      (node (ref "R70") (pin "2") (pinfunction "2_2") (pintype "passive"))
    )
    (net (code "29") (name "Net-(D3-PadA)") (class "Default")
      (node (ref "D3") (pin "A") (pinfunction "A_A") (pintype "passive"))
      (node (ref "JP8") (pin "10") (pinfunction "10_10") (pintype "passive"))
    )
    (net (code "30") (name "Net-(D4-PadA)") (class "Default")
      (node (ref "D4") (pin "A") (pinfunction "A_A") (pintype "passive"))
      (node (ref "L1") (pin "2") (pinfunction "2_2") (pintype "passive"))
    )
    (net (code "31") (name "Net-(D4-PadC)") (class "Default")
      (node (ref "D4") (pin "C") (pinfunction "C_C") (pintype "passive"))
      (node (ref "JP8") (pin "2") (pinfunction "2_2") (pintype "passive"))
    )
    (net (code "32") (name "Net-(D5-PadC)") (class "Default")
      (node (ref "D5") (pin "C") (pinfunction "C_C") (pintype "passive"))
      (node (ref "Q6") (pin "B") (pinfunction "B_B") (pintype "passive"))
      (node (ref "R68") (pin "2") (pinfunction "2_2") (pintype "passive"))
      (node (ref "R71") (pin "2") (pinfunction "2_2") (pintype "passive"))
    )
    (net (code "33") (name "Net-(IC1-IREF)") (class "Default")
      (node (ref "IC1") (pin "23") (pinfunction "IREF_23") (pintype "bidirectional"))
      (node (ref "R50") (pin "1") (pinfunction "1_1") (pintype "passive"))
    )
    (net (code "34") (name "Net-(IC1-OUT1)") (class "Default")
      (node (ref "IC1") (pin "6") (pinfunction "OUT1_6") (pintype "bidirectional"))
      (node (ref "R31") (pin "2") (pinfunction "2_2") (pintype "passive"))
    )
    (net (code "35") (name "Net-(IC1-OUT2)") (class "Default")
      (node (ref "IC1") (pin "7") (pinfunction "OUT2_7") (pintype "bidirectional"))
      (node (ref "MODE_C") (pin "RED_C") (pinfunction "RED_RED_C") (pintype "bidirectional"))
    )
    (net (code "36") (name "Net-(IC1-OUT3)") (class "Default")
      (node (ref "IC1") (pin "8") (pinfunction "OUT3_8") (pintype "bidirectional"))
      (node (ref "MODE_C") (pin "GREEN_C") (pinfunction "GRN_GREEN_C") (pintype "bidirectional"))
    )
    (net (code "37") (name "Net-(IC1-OUT4)") (class "Default")
      (node (ref "IC1") (pin "9") (pinfunction "OUT4_9") (pintype "bidirectional"))
      (node (ref "MODE_A") (pin "GREEN_C") (pinfunction "GRN_GREEN_C") (pintype "bidirectional"))
    )
    (net (code "38") (name "Net-(IC1-OUT5)") (class "Default")
      (node (ref "IC1") (pin "10") (pinfunction "OUT5_10") (pintype "bidirectional"))
      (node (ref "MODE_A") (pin "RED_C") (pinfunction "RED_RED_C") (pintype "bidirectional"))
    )
    (net (code "39") (name "Net-(IC1-OUT6)") (class "Default")
      (node (ref "IC1") (pin "11") (pinfunction "OUT6_11") (pintype "bidirectional"))
      (node (ref "MODE_B") (pin "GREEN_C") (pinfunction "GRN_GREEN_C") (pintype "bidirectional"))
    )
    (net (code "40") (name "Net-(IC1-OUT7)") (class "Default")
      (node (ref "IC1") (pin "12") (pinfunction "OUT7_12") (pintype "bidirectional"))
      (node (ref "MODE_B") (pin "RED_C") (pinfunction "RED_RED_C") (pintype "bidirectional"))
    )
    (net (code "41") (name "Net-(IC1-OUT8)") (class "Default")
      (node (ref "IC1") (pin "13") (pinfunction "OUT8_13") (pintype "bidirectional"))
      (node (ref "LED10") (pin "GREEN_C") (pinfunction "GRN_GREEN_C") (pintype "bidirectional"))
    )
    (net (code "42") (name "Net-(IC1-OUT9)") (class "Default")
      (node (ref "IC1") (pin "14") (pinfunction "OUT9_14") (pintype "bidirectional"))
      (node (ref "LED10") (pin "RED_C") (pinfunction "RED_RED_C") (pintype "bidirectional"))
    )
    (net (code "43") (name "Net-(IC1-OUT10)") (class "Default")
      (node (ref "IC1") (pin "15") (pinfunction "OUT10_15") (pintype "bidirectional"))
      (node (ref "LED11") (pin "RED_C") (pinfunction "RED_RED_C") (pintype "bidirectional"))
    )
    (net (code "44") (name "Net-(IC1-OUT11)") (class "Default")
      (node (ref "IC1") (pin "16") (pinfunction "OUT11_16") (pintype "bidirectional"))
      (node (ref "LED11") (pin "GREEN_C") (pinfunction "GRN_GREEN_C") (pintype "bidirectional"))
    )
    (net (code "45") (name "Net-(IC1-OUT12)") (class "Default")
      (node (ref "IC1") (pin "17") (pinfunction "OUT12_17") (pintype "bidirectional"))
      (node (ref "LED12") (pin "RED_C") (pinfunction "RED_RED_C") (pintype "bidirectional"))
    )
    (net (code "46") (name "Net-(IC1-OUT13)") (class "Default")
      (node (ref "IC1") (pin "18") (pinfunction "OUT13_18") (pintype "bidirectional"))
      (node (ref "LED12") (pin "GREEN_C") (pinfunction "GRN_GREEN_C") (pintype "bidirectional"))
    )
    (net (code "47") (name "Net-(IC1-OUT14)") (class "Default")
      (node (ref "IC1") (pin "19") (pinfunction "OUT14_19") (pintype "bidirectional"))
      (node (ref "R19") (pin "2") (pinfunction "2_2") (pintype "passive"))
    )
    (net (code "48") (name "Net-(IC1-OUT15)") (class "Default")
      (node (ref "IC1") (pin "20") (pinfunction "OUT15_20") (pintype "bidirectional"))
      (node (ref "R30") (pin "2") (pinfunction "2_2") (pintype "passive"))
    )
    (net (code "49") (name "Net-(IC1-VCC)") (class "Default")
      (node (ref "C7") (pin "1") (pinfunction "1_1") (pintype "passive"))
      (node (ref "C8") (pin "1") (pinfunction "1_1") (pintype "passive"))
      (node (ref "IC1") (pin "24") (pinfunction "VCC_24") (pintype "bidirectional"))
      (node (ref "L2") (pin "1") (pinfunction "1_1") (pintype "passive"))
    )
    (net (code "50") (name "Net-(IC2-VI)") (class "Default")
      (node (ref "C19") (pin "1") (pinfunction "1_1") (pintype "passive"))
      (node (ref "IC2") (pin "1") (pinfunction "VI_1") (pintype "input"))
      (node (ref "L3") (pin "2") (pinfunction "2_2") (pintype "passive"))
    )
    (net (code "51") (name "Net-(IC3A-X0)") (class "Default")
      (node (ref "IC3") (pin "13") (pinfunction "X0_13") (pintype "bidirectional"))
      (node (ref "POT_C") (pin "P$2") (pinfunction "S_P$2") (pintype "passive"))
    )
    (net (code "52") (name "Net-(IC3A-X1)") (class "Default")
      (node (ref "IC3") (pin "14") (pinfunction "X1_14") (pintype "bidirectional"))
      (node (ref "SLD_C") (pin "2") (pinfunction "S_2") (pintype "passive"))
    )
    (net (code "53") (name "Net-(IC3A-X2)") (class "Default")
      (node (ref "IC3") (pin "15") (pinfunction "X2_15") (pintype "bidirectional"))
      (node (ref "SLD_B") (pin "2") (pinfunction "S_2") (pintype "passive"))
    )
    (net (code "54") (name "Net-(IC3A-X3)") (class "Default")
      (node (ref "IC3") (pin "12") (pinfunction "X3_12") (pintype "bidirectional"))
      (node (ref "POT_A") (pin "P$2") (pinfunction "S_P$2") (pintype "passive"))
    )
    (net (code "55") (name "Net-(IC3A-X4)") (class "Default")
      (node (ref "IC3") (pin "1") (pinfunction "X4_1") (pintype "bidirectional"))
      (node (ref "SLD_A") (pin "2") (pinfunction "S_2") (pintype "passive"))
    )
    (net (code "56") (name "Net-(IC3A-X6)") (class "Default")
      (node (ref "IC3") (pin "2") (pinfunction "X6_2") (pintype "bidirectional"))
      (node (ref "POT_B") (pin "P$2") (pinfunction "S_P$2") (pintype "passive"))
    )
    (net (code "57") (name "Net-(IC7-VI)") (class "Default")
      (node (ref "C20") (pin "1") (pinfunction "1_1") (pintype "passive"))
      (node (ref "IC7") (pin "3") (pinfunction "VI_3") (pintype "input"))
      (node (ref "L4") (pin "1") (pinfunction "1_1") (pintype "passive"))
    )
    (net (code "58") (name "Net-(IC9A-+IN)") (class "Default")
      (node (ref "IC9") (pin "3") (pinfunction "+IN_3") (pintype "input"))
      (node (ref "R8") (pin "2") (pinfunction "2_2") (pintype "passive"))
      (node (ref "R9") (pin "1") (pinfunction "1_1") (pintype "passive"))
    )
    (net (code "59") (name "Net-(IC9A--IN)") (class "Default")
      (node (ref "IC9") (pin "2") (pinfunction "-IN_2") (pintype "input"))
      (node (ref "R10") (pin "1") (pinfunction "1_1") (pintype "passive"))
    )
    (net (code "60") (name "Net-(IC9A-OUT)") (class "Default")
      (node (ref "IC9") (pin "1") (pinfunction "OUT_1") (pintype "output"))
      (node (ref "R7") (pin "2") (pinfunction "2_2") (pintype "passive"))
      (node (ref "R8") (pin "1") (pinfunction "1_1") (pintype "passive"))
    )
    (net (code "61") (name "Net-(IC9B-+IN)") (class "Default")
      (node (ref "IC9") (pin "5") (pinfunction "+IN_5") (pintype "input"))
      (node (ref "R12") (pin "2") (pinfunction "2_2") (pintype "passive"))
      (node (ref "R13") (pin "1") (pinfunction "1_1") (pintype "passive"))
    )
    (net (code "62") (name "Net-(IC9B--IN)") (class "Default")
      (node (ref "IC9") (pin "6") (pinfunction "-IN_6") (pintype "input"))
      (node (ref "R14") (pin "1") (pinfunction "1_1") (pintype "passive"))
    )
    (net (code "63") (name "Net-(IC9B-OUT)") (class "Default")
      (node (ref "IC9") (pin "7") (pinfunction "OUT_7") (pintype "output"))
      (node (ref "R11") (pin "2") (pinfunction "2_2") (pintype "passive"))
      (node (ref "R12") (pin "1") (pinfunction "1_1") (pintype "passive"))
    )
    (net (code "64") (name "Net-(IC9C-+IN)") (class "Default")
      (node (ref "IC9") (pin "10") (pinfunction "+IN_10") (pintype "input"))
      (node (ref "R16") (pin "2") (pinfunction "2_2") (pintype "passive"))
      (node (ref "R17") (pin "1") (pinfunction "1_1") (pintype "passive"))
    )
    (net (code "65") (name "Net-(IC9C--IN)") (class "Default")
      (node (ref "IC9") (pin "9") (pinfunction "-IN_9") (pintype "input"))
      (node (ref "R20") (pin "1") (pinfunction "1_1") (pintype "passive"))
    )
    (net (code "66") (name "Net-(IC9C-OUT)") (class "Default")
      (node (ref "IC9") (pin "8") (pinfunction "OUT_8") (pintype "output"))
      (node (ref "R15") (pin "2") (pinfunction "2_2") (pintype "passive"))
      (node (ref "R16") (pin "1") (pinfunction "1_1") (pintype "passive"))
    )
    (net (code "67") (name "Net-(IC9D--IN)") (class "Default")
      (node (ref "IC9") (pin "13") (pinfunction "-IN_13") (pintype "input"))
      (node (ref "IC9") (pin "14") (pinfunction "OUT_14") (pintype "output"))
    )
    (net (code "68") (name "Net-(J1-3)") (class "Default")
      (node (ref "C27") (pin "1") (pinfunction "1_1") (pintype "passive"))
      (node (ref "J1") (pin "P3") (pinfunction "3_P3") (pintype "passive"))
      (node (ref "R6") (pin "2") (pinfunction "2_2") (pintype "passive"))
    )
    (net (code "69") (name "Net-(J2-3)") (class "Default")
      (node (ref "C29") (pin "1") (pinfunction "1_1") (pintype "passive"))
      (node (ref "J2") (pin "P3") (pinfunction "3_P3") (pintype "passive"))
      (node (ref "R51") (pin "2") (pinfunction "2_2") (pintype "passive"))
    )
    (net (code "70") (name "Net-(J3-3)") (class "Default")
      (node (ref "J3") (pin "P3") (pinfunction "3_P3") (pintype "passive"))
      (node (ref "R68") (pin "1") (pinfunction "1_1") (pintype "passive"))
    )
    (net (code "71") (name "Net-(J4-3)") (class "Default")
      (node (ref "J4") (pin "P3") (pinfunction "3_P3") (pintype "passive"))
      (node (ref "R67") (pin "1") (pinfunction "1_1") (pintype "passive"))
    )
    (net (code "72") (name "Net-(J5-3)") (class "Default")
      (node (ref "C25") (pin "1") (pinfunction "1_1") (pintype "passive"))
      (node (ref "J5") (pin "P3") (pinfunction "3_P3") (pintype "passive"))
      (node (ref "R4") (pin "2") (pinfunction "2_2") (pintype "passive"))
    )
    (net (code "73") (name "Net-(J6-3)") (class "Default")
      (node (ref "J6") (pin "P3") (pinfunction "3_P3") (pintype "passive"))
      (node (ref "R66") (pin "1") (pinfunction "1_1") (pintype "passive"))
    )
    (net (code "74") (name "Net-(J7-3)") (class "Default")
      (node (ref "J7") (pin "P3") (pinfunction "3_P3") (pintype "passive"))
      (node (ref "R35") (pin "1") (pinfunction "1_1") (pintype "passive"))
      (node (ref "R41") (pin "1") (pinfunction "1_1") (pintype "passive"))
    )
    (net (code "75") (name "Net-(J8-3)") (class "Default")
      (node (ref "J8") (pin "P3") (pinfunction "3_P3") (pintype "passive"))
      (node (ref "R32") (pin "1") (pinfunction "1_1") (pintype "passive"))
      (node (ref "R33") (pin "1") (pinfunction "1_1") (pintype "passive"))
    )
    (net (code "76") (name "Net-(J9-3)") (class "Default")
      (node (ref "J9") (pin "P3") (pinfunction "3_P3") (pintype "passive"))
      (node (ref "R36") (pin "1") (pinfunction "1_1") (pintype "passive"))
      (node (ref "R37") (pin "1") (pinfunction "1_1") (pintype "passive"))
    )
    (net (code "77") (name "Net-(J10-3)") (class "Default")
      (node (ref "J10") (pin "P3") (pinfunction "3_P3") (pintype "passive"))
      (node (ref "R7") (pin "1") (pinfunction "1_1") (pintype "passive"))
    )
    (net (code "78") (name "Net-(J11-3)") (class "Default")
      (node (ref "J11") (pin "P3") (pinfunction "3_P3") (pintype "passive"))
      (node (ref "R11") (pin "1") (pinfunction "1_1") (pintype "passive"))
    )
    (net (code "79") (name "Net-(J12-3)") (class "Default")
      (node (ref "J12") (pin "P3") (pinfunction "3_P3") (pintype "passive"))
      (node (ref "R15") (pin "1") (pinfunction "1_1") (pintype "passive"))
    )
    (net (code "80") (name "Net-(Q2B-2)") (class "Default")
      (node (ref "C35") (pin "2") (pinfunction "2_2") (pintype "passive"))
      (node (ref "Q2") (pin "3") (pinfunction "2_3") (pintype "passive"))
      (node (ref "R21") (pin "2") (pinfunction "2_2") (pintype "passive"))
    )
    (net (code "81") (name "Net-(SLD_AA-C)") (class "Default")
      (node (ref "R19") (pin "1") (pinfunction "1_1") (pintype "passive"))
      (node (ref "SLD_A") (pin "E") (pinfunction "C_E") (pintype "passive"))
    )
    (net (code "82") (name "Net-(SLD_BA-C)") (class "Default")
      (node (ref "R30") (pin "1") (pinfunction "1_1") (pintype "passive"))
      (node (ref "SLD_B") (pin "E") (pinfunction "C_E") (pintype "passive"))
    )
    (net (code "83") (name "Net-(SLD_CA-C)") (class "Default")
      (node (ref "R31") (pin "1") (pinfunction "1_1") (pintype "passive"))
      (node (ref "SLD_C") (pin "E") (pinfunction "C_E") (pintype "passive"))
    )
    (net (code "84") (name "Net-(U1-PF0{slash}OSC_IN)") (class "Default")
      (node (ref "R21") (pin "1") (pinfunction "1_1") (pintype "passive"))
      (node (ref "U1") (pin "2") (pinfunction "PF0/OSC_IN_2") (pintype "bidirectional"))
    )
    (net (code "85") (name "Net-(U1-PF1{slash}OSC_OUT)") (class "Default")
      (node (ref "R22") (pin "1") (pinfunction "1_1") (pintype "passive"))
      (node (ref "U1") (pin "3") (pinfunction "PF1/OSC_OUT_3") (pintype "bidirectional"))
    )
    (net (code "86") (name "Net-(U2A-+IN)") (class "Default")
      (node (ref "C12") (pin "1") (pinfunction "1_1") (pintype "passive"))
      (node (ref "R29") (pin "1") (pinfunction "1_1") (pintype "passive"))
      (node (ref "R4") (pin "1") (pinfunction "1_1") (pintype "passive"))
      (node (ref "R5") (pin "2") (pinfunction "2_2") (pintype "passive"))
      (node (ref "U2") (pin "3") (pinfunction "+IN_3") (pintype "input"))
    )
    (net (code "87") (name "Net-(U2B-+IN)") (class "Default")
      (node (ref "C26") (pin "1") (pinfunction "1_1") (pintype "passive"))
      (node (ref "R26") (pin "2") (pinfunction "2_2") (pintype "passive"))
      (node (ref "R28") (pin "1") (pinfunction "1_1") (pintype "passive"))
      (node (ref "R6") (pin "1") (pinfunction "1_1") (pintype "passive"))
      (node (ref "U2") (pin "5") (pinfunction "+IN_5") (pintype "input"))
    )
    (net (code "88") (name "Net-(U2C-+IN)") (class "Default")
      (node (ref "C28") (pin "1") (pinfunction "1_1") (pintype "passive"))
      (node (ref "R51") (pin "1") (pinfunction "1_1") (pintype "passive"))
      (node (ref "R52") (pin "2") (pinfunction "2_2") (pintype "passive"))
      (node (ref "R53") (pin "1") (pinfunction "1_1") (pintype "passive"))
      (node (ref "U2") (pin "10") (pinfunction "+IN_10") (pintype "input"))
    )
    (net (code "89") (name "Net-(U2D-+IN)") (class "Default")
      (node (ref "U2") (pin "12") (pinfunction "+IN_12") (pintype "input"))
      (node (ref "U2") (pin "14") (pinfunction "OUT_14") (pintype "output"))
    )
    (net (code "90") (name "Net-(U4A-+IN)") (class "Default")
      (node (ref "C1") (pin "1") (pinfunction "1_1") (pintype "passive"))
      (node (ref "R41") (pin "2") (pinfunction "2_2") (pintype "passive"))
      (node (ref "R47") (pin "1") (pinfunction "1_1") (pintype "passive"))
      (node (ref "U4") (pin "3") (pinfunction "+IN_3") (pintype "input"))
    )
    (net (code "91") (name "Net-(U4A-OUT)") (class "Default")
      (node (ref "C1") (pin "2") (pinfunction "2_2") (pintype "passive"))
      (node (ref "R35") (pin "2") (pinfunction "2_2") (pintype "passive"))
      (node (ref "U4") (pin "1") (pinfunction "OUT_1") (pintype "output"))
    )
    (net (code "92") (name "Net-(U4B-+IN)") (class "Default")
      (node (ref "C2") (pin "1") (pinfunction "1_1") (pintype "passive"))
      (node (ref "R33") (pin "2") (pinfunction "2_2") (pintype "passive"))
      (node (ref "R34") (pin "1") (pinfunction "1_1") (pintype "passive"))
      (node (ref "U4") (pin "5") (pinfunction "+IN_5") (pintype "input"))
    )
    (net (code "93") (name "Net-(U4B-OUT)") (class "Default")
      (node (ref "C2") (pin "2") (pinfunction "2_2") (pintype "passive"))
      (node (ref "R32") (pin "2") (pinfunction "2_2") (pintype "passive"))
      (node (ref "U4") (pin "7") (pinfunction "OUT_7") (pintype "output"))
    )
    (net (code "94") (name "Net-(U4C-+IN)") (class "Default")
      (node (ref "C3") (pin "1") (pinfunction "1_1") (pintype "passive"))
      (node (ref "R37") (pin "2") (pinfunction "2_2") (pintype "passive"))
      (node (ref "R38") (pin "1") (pinfunction "1_1") (pintype "passive"))
      (node (ref "U4") (pin "10") (pinfunction "+IN_10") (pintype "input"))
    )
    (net (code "95") (name "Net-(U4C-OUT)") (class "Default")
      (node (ref "C3") (pin "2") (pinfunction "2_2") (pintype "passive"))
      (node (ref "R36") (pin "2") (pinfunction "2_2") (pintype "passive"))
      (node (ref "U4") (pin "8") (pinfunction "OUT_8") (pintype "output"))
    )
    (net (code "96") (name "Net-(U4D-+IN)") (class "Default")
      (node (ref "U4") (pin "12") (pinfunction "+IN_12") (pintype "input"))
      (node (ref "U4") (pin "14") (pinfunction "OUT_14") (pintype "output"))
    )
    (net (code "97") (name "POTS_ADDR_A") (class "Default")
      (node (ref "IC3") (pin "11") (pinfunction "A_11") (pintype "input"))
      (node (ref "U1") (pin "13") (pinfunction "PA7_13") (pintype "bidirectional"))
    )
    (net (code "98") (name "POTS_ADDR_B") (class "Default")
      (node (ref "IC3") (pin "10") (pinfunction "B_10") (pintype "input"))
      (node (ref "U1") (pin "18") (pinfunction "PA8_18") (pintype "bidirectional"))
    )
    (net (code "99") (name "POTS_ADDR_C") (class "Default")
      (node (ref "IC3") (pin "9") (pinfunction "C_9") (pintype "input"))
      (node (ref "U1") (pin "19") (pinfunction "PA9_19") (pintype "bidirectional"))
    )
    (net (code "100") (name "RESET") (class "Default")
      (node (ref "C36") (pin "1") (pinfunction "1_1") (pintype "passive"))
      (node (ref "JP6") (pin "4") (pinfunction "4_4") (pintype "passive"))
      (node (ref "R18") (pin "2") (pinfunction "2_2") (pintype "passive"))
      (node (ref "U1") (pin "4") (pinfunction "NRST_4") (pintype "bidirectional"))
    )
    (net (code "101") (name "SWCLK") (class "Default")
      (node (ref "JP6") (pin "3") (pinfunction "3_3") (pintype "passive"))
      (node (ref "U1") (pin "24") (pinfunction "PA14_24") (pintype "bidirectional"))
    )
    (net (code "102") (name "SWDIO") (class "Default")
      (node (ref "JP6") (pin "2") (pinfunction "2_2") (pintype "passive"))
      (node (ref "U1") (pin "23") (pinfunction "PA13_23") (pintype "bidirectional"))
    )
    (net (code "103") (name "SW_MODE_A") (class "Default")
      (node (ref "SW_A") (pin "3") (pinfunction "3_3") (pintype "passive"))
      (node (ref "SW_A") (pin "4") (pinfunction "4_4") (pintype "passive"))
      (node (ref "U1") (pin "27") (pinfunction "PB4_27") (pintype "bidirectional"))
    )
    (net (code "104") (name "SW_MODE_B") (class "Default")
      (node (ref "SW_B") (pin "3") (pinfunction "3_3") (pintype "passive"))
      (node (ref "SW_B") (pin "4") (pinfunction "4_4") (pintype "passive"))
      (node (ref "U1") (pin "29") (pinfunction "PB6_29") (pintype "bidirectional"))
    )
    (net (code "105") (name "SW_MODE_C") (class "Default")
      (node (ref "SW_C") (pin "3") (pinfunction "3_3") (pintype "passive"))
      (node (ref "SW_C") (pin "4") (pinfunction "4_4") (pintype "passive"))
      (node (ref "U1") (pin "30") (pinfunction "PB7_30") (pintype "bidirectional"))
    )
    (net (code "106") (name "VCC") (class "Default")
      (node (ref "C14") (pin "1") (pinfunction "1_1") (pintype "passive"))
      (node (ref "C21") (pin "1") (pinfunction "1_1") (pintype "passive"))
      (node (ref "C4") (pin "1") (pinfunction "1_1") (pintype "passive"))
      (node (ref "C50") (pin "1") (pinfunction "1_1") (pintype "passive"))
      (node (ref "IC4") (pin "4") (pinfunction "V+_4") (pintype "power_in"))
      (node (ref "L5") (pin "1") (pinfunction "1_1") (pintype "passive"))
      (node (ref "U4") (pin "4") (pinfunction "V+_4") (pintype "power_in"))
    )
    (net (code "107") (name "VEE") (class "Default")
      (node (ref "C16") (pin "2") (pinfunction "2_2") (pintype "passive"))
      (node (ref "C18") (pin "2") (pinfunction "2_2") (pintype "passive"))
      (node (ref "C23") (pin "2") (pinfunction "2_2") (pintype "passive"))
      (node (ref "L1") (pin "1") (pinfunction "1_1") (pintype "passive"))
      (node (ref "R1") (pin "1") (pinfunction "1_1") (pintype "passive"))
      (node (ref "U4") (pin "11") (pinfunction "V-_11") (pintype "power_in"))
    )
    (net (code "108") (name "VREF_BIAS") (class "Default")
      (node (ref "C22") (pin "+") (pinfunction "+_+") (pintype "passive"))
      (node (ref "U$1") (pin "2") (pinfunction "VOUT_2") (pintype "output"))
      (node (ref "U4") (pin "2") (pinfunction "-IN_2") (pintype "input"))
      (node (ref "U4") (pin "6") (pinfunction "-IN_6") (pintype "input"))
      (node (ref "U4") (pin "9") (pinfunction "-IN_9") (pintype "input"))
    )
    (net (code "109") (name "unconnected-(IC1-LAT-Pad4)") (class "Default")
      (node (ref "IC1") (pin "4") (pinfunction "LAT_4") (pintype "bidirectional"))
    )
    (net (code "110") (name "unconnected-(IC1-OUT0-Pad5)") (class "Default")
      (node (ref "IC1") (pin "5") (pinfunction "OUT0_5") (pintype "bidirectional"))
    )
    (net (code "111") (name "unconnected-(IC1-SOUT-Pad22)") (class "Default")
      (node (ref "IC1") (pin "22") (pinfunction "SOUT_22") (pintype "bidirectional"))
    )
    (net (code "112") (name "unconnected-(IC2-EN-Pad4)") (class "Default")
      (node (ref "IC2") (pin "4") (pinfunction "EN_4") (pintype "input"))
    )
    (net (code "113") (name "unconnected-(IC3A-X5-Pad5)") (class "Default")
      (node (ref "IC3") (pin "5") (pinfunction "X5_5") (pintype "bidirectional"))
    )
    (net (code "114") (name "unconnected-(IC3A-X7-Pad4)") (class "Default")
      (node (ref "IC3") (pin "4") (pinfunction "X7_4") (pintype "bidirectional"))
    )
    (net (code "115") (name "unconnected-(J7-2-PadP2)") (class "Default")
      (node (ref "J7") (pin "P2") (pinfunction "2_P2") (pintype "passive"))
    )
    (net (code "116") (name "unconnected-(J8-2-PadP2)") (class "Default")
      (node (ref "J8") (pin "P2") (pinfunction "2_P2") (pintype "passive"))
    )
    (net (code "117") (name "unconnected-(J9-2-PadP2)") (class "Default")
      (node (ref "J9") (pin "P2") (pinfunction "2_P2") (pintype "passive"))
    )
    (net (code "118") (name "unconnected-(J10-2-PadP2)") (class "Default")
      (node (ref "J10") (pin "P2") (pinfunction "2_P2") (pintype "passive"))
    )
    (net (code "119") (name "unconnected-(J11-2-PadP2)") (class "Default")
      (node (ref "J11") (pin "P2") (pinfunction "2_P2") (pintype "passive"))
    )
    (net (code "120") (name "unconnected-(J12-2-PadP2)") (class "Default")
      (node (ref "J12") (pin "P2") (pinfunction "2_P2") (pintype "passive"))
    )
    (net (code "121") (name "unconnected-(JP8-Pad1)") (class "Default")
      (node (ref "JP8") (pin "1") (pinfunction "1_1") (pintype "passive"))
    )
    (net (code "122") (name "unconnected-(JP8-Pad9)") (class "Default")
      (node (ref "JP8") (pin "9") (pinfunction "9_9") (pintype "passive"))
    )
  )
)
